# R302L.net
KiCad netlist of a schematic drawn in EAGLE
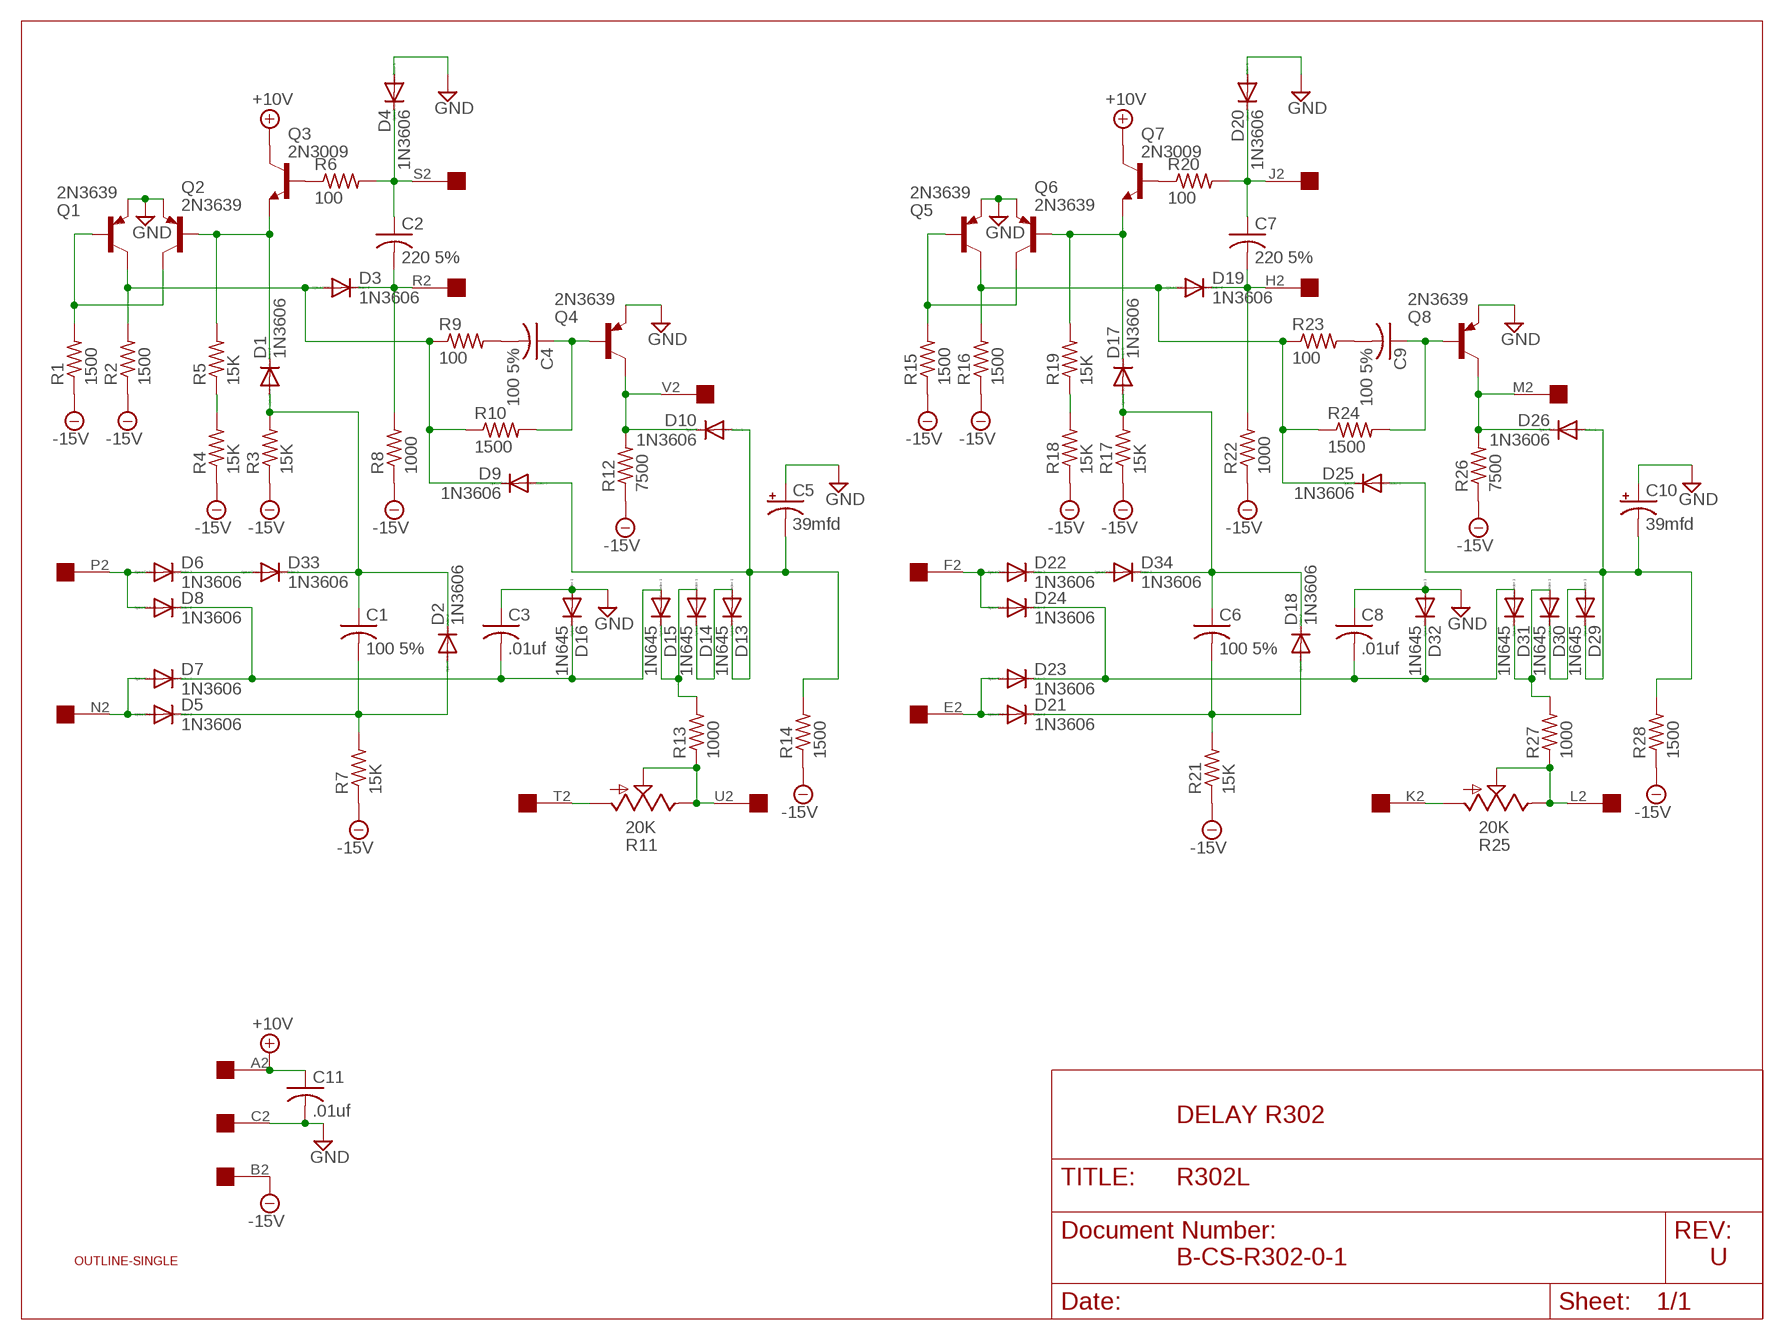
[diagram p0: schematic, sheet 1]

(export (version "E")
  (design (tool "Eeschema 10.0.6"))
  (components
    (comp (ref "C1")
      (value "100 5%")
      (footprint "eagle-import:C050-025X075")
      (libsource (lib "eagle-import") (part "C-US050-025X075"))
    )
    (comp (ref "C2")
      (value "220 5%")
      (footprint "eagle-import:C050-025X075")
      (libsource (lib "eagle-import") (part "C-US050-025X075"))
    )
    (comp (ref "C3")
      (value ".01uf")
      (footprint "eagle-import:C050-025X075")
      (libsource (lib "eagle-import") (part "C-US050-025X075"))
    )
    (comp (ref "C4")
      (value "100 5%")
      (footprint "eagle-import:C050-025X075")
      (libsource (lib "eagle-import") (part "C-US050-025X075"))
    )
    (comp (ref "C5")
      (value "39mfd")
      (footprint "eagle-import:E15-5")
      (libsource (lib "eagle-import") (part "CPOL-USE15-5AXIAL"))
    )
    (comp (ref "C6")
      (value "100 5%")
      (footprint "eagle-import:C050-025X075")
      (libsource (lib "eagle-import") (part "C-US050-025X075"))
    )
    (comp (ref "C7")
      (value "220 5%")
      (footprint "eagle-import:C050-025X075")
      (libsource (lib "eagle-import") (part "C-US050-025X075"))
    )
    (comp (ref "C8")
      (value ".01uf")
      (footprint "eagle-import:C050-025X075")
      (libsource (lib "eagle-import") (part "C-US050-025X075"))
    )
    (comp (ref "C9")
      (value "100 5%")
      (footprint "eagle-import:C050-025X075")
      (libsource (lib "eagle-import") (part "C-US050-025X075"))
    )
    (comp (ref "C10")
      (value "39mfd")
      (footprint "eagle-import:E15-5")
      (libsource (lib "eagle-import") (part "CPOL-USE15-5AXIAL"))
    )
    (comp (ref "C11")
      (value ".01uf")
      (footprint "eagle-import:C050-025X075")
      (libsource (lib "eagle-import") (part "C-US050-025X075"))
    )
    (comp (ref "D1")
      (value "1N3606")
      (footprint "eagle-import:DO35-10")
      (libsource (lib "eagle-import") (part "1N4148DO35-10"))
    )
    (comp (ref "D2")
      (value "1N3606")
      (footprint "eagle-import:DO35-10")
      (libsource (lib "eagle-import") (part "1N4148DO35-10"))
    )
    (comp (ref "D3")
      (value "1N3606")
      (footprint "eagle-import:DO35-10")
      (libsource (lib "eagle-import") (part "1N4148DO35-10"))
    )
    (comp (ref "D4")
      (value "1N3606")
      (footprint "eagle-import:DO35-10")
      (libsource (lib "eagle-import") (part "1N4148DO35-10"))
    )
    (comp (ref "D5")
      (value "1N3606")
      (footprint "eagle-import:DO35-10")
      (libsource (lib "eagle-import") (part "1N4148DO35-10"))
    )
    (comp (ref "D6")
      (value "1N3606")
      (footprint "eagle-import:DO35-10")
      (libsource (lib "eagle-import") (part "1N4148DO35-10"))
    )
    (comp (ref "D7")
      (value "1N3606")
      (footprint "eagle-import:DO35-10")
      (libsource (lib "eagle-import") (part "1N4148DO35-10"))
    )
    (comp (ref "D8")
      (value "1N3606")
      (footprint "eagle-import:DO35-10")
      (libsource (lib "eagle-import") (part "1N4148DO35-10"))
    )
    (comp (ref "D9")
      (value "1N3606")
      (footprint "eagle-import:DO35-10")
      (libsource (lib "eagle-import") (part "1N4148DO35-10"))
    )
    (comp (ref "D10")
      (value "1N3606")
      (footprint "eagle-import:DO35-10")
      (libsource (lib "eagle-import") (part "1N4148DO35-10"))
    )
    (comp (ref "D13")
      (value "1N645")
      (footprint "eagle-import:DO35-10")
      (libsource (lib "eagle-import") (part "1N4148DO35-10"))
    )
    (comp (ref "D14")
      (value "1N645")
      (footprint "eagle-import:DO35-10")
      (libsource (lib "eagle-import") (part "1N4148DO35-10"))
    )
    (comp (ref "D15")
      (value "1N645")
      (footprint "eagle-import:DO35-10")
      (libsource (lib "eagle-import") (part "1N4148DO35-10"))
    )
    (comp (ref "D16")
      (value "1N645")
      (footprint "eagle-import:DO35-10")
      (libsource (lib "eagle-import") (part "1N4148DO35-10"))
    )
    (comp (ref "D17")
      (value "1N3606")
      (footprint "eagle-import:DO35-10")
      (libsource (lib "eagle-import") (part "1N4148DO35-10"))
    )
    (comp (ref "D18")
      (value "1N3606")
      (footprint "eagle-import:DO35-10")
      (libsource (lib "eagle-import") (part "1N4148DO35-10"))
    )
    (comp (ref "D19")
      (value "1N3606")
      (footprint "eagle-import:DO35-10")
      (libsource (lib "eagle-import") (part "1N4148DO35-10"))
    )
    (comp (ref "D20")
      (value "1N3606")
      (footprint "eagle-import:DO35-10")
      (libsource (lib "eagle-import") (part "1N4148DO35-10"))
    )
    (comp (ref "D21")
      (value "1N3606")
      (footprint "eagle-import:DO35-10")
      (libsource (lib "eagle-import") (part "1N4148DO35-10"))
    )
    (comp (ref "D22")
      (value "1N3606")
      (footprint "eagle-import:DO35-10")
      (libsource (lib "eagle-import") (part "1N4148DO35-10"))
    )
    (comp (ref "D23")
      (value "1N3606")
      (footprint "eagle-import:DO35-10")
      (libsource (lib "eagle-import") (part "1N4148DO35-10"))
    )
    (comp (ref "D24")
      (value "1N3606")
      (footprint "eagle-import:DO35-10")
      (libsource (lib "eagle-import") (part "1N4148DO35-10"))
    )
    (comp (ref "D25")
      (value "1N3606")
      (footprint "eagle-import:DO35-10")
      (libsource (lib "eagle-import") (part "1N4148DO35-10"))
    )
    (comp (ref "D26")
      (value "1N3606")
      (footprint "eagle-import:DO35-10")
      (libsource (lib "eagle-import") (part "1N4148DO35-10"))
    )
    (comp (ref "D29")
      (value "1N645")
      (footprint "eagle-import:DO35-10")
      (libsource (lib "eagle-import") (part "1N4148DO35-10"))
    )
    (comp (ref "D30")
      (value "1N645")
      (footprint "eagle-import:DO35-10")
      (libsource (lib "eagle-import") (part "1N4148DO35-10"))
    )
    (comp (ref "D31")
      (value "1N645")
      (footprint "eagle-import:DO35-10")
      (libsource (lib "eagle-import") (part "1N4148DO35-10"))
    )
    (comp (ref "D32")
      (value "1N645")
      (footprint "eagle-import:DO35-10")
      (libsource (lib "eagle-import") (part "1N4148DO35-10"))
    )
    (comp (ref "D33")
      (value "1N3606")
      (footprint "eagle-import:DO35-10")
      (libsource (lib "eagle-import") (part "1N4148DO35-10"))
    )
    (comp (ref "D34")
      (value "1N3606")
      (footprint "eagle-import:DO35-10")
      (libsource (lib "eagle-import") (part "1N4148DO35-10"))
    )
    (comp (ref "Q1")
      (value "2N3639")
      (footprint "eagle-import:TO39")
      (libsource (lib "eagle-import") (part "2N3637"))
    )
    (comp (ref "Q2")
      (value "2N3639")
      (footprint "eagle-import:TO39")
      (libsource (lib "eagle-import") (part "2N3637"))
    )
    (comp (ref "Q3")
      (value "2N3009")
      (footprint "eagle-import:TO39")
      (libsource (lib "eagle-import") (part "-NPN-TO39-EBC2N3019"))
    )
    (comp (ref "Q4")
      (value "2N3639")
      (footprint "eagle-import:TO39")
      (libsource (lib "eagle-import") (part "2N3637"))
    )
    (comp (ref "Q5")
      (value "2N3639")
      (footprint "eagle-import:TO39")
      (libsource (lib "eagle-import") (part "2N3637"))
    )
    (comp (ref "Q6")
      (value "2N3639")
      (footprint "eagle-import:TO39")
      (libsource (lib "eagle-import") (part "2N3637"))
    )
    (comp (ref "Q7")
      (value "2N3009")
      (footprint "eagle-import:TO39")
      (libsource (lib "eagle-import") (part "-NPN-TO39-EBC2N3019"))
    )
    (comp (ref "Q8")
      (value "2N3639")
      (footprint "eagle-import:TO39")
      (libsource (lib "eagle-import") (part "2N3637"))
    )
    (comp (ref "R1")
      (value "1500")
      (footprint "eagle-import:0207_10")
      (libsource (lib "eagle-import") (part "R-US_0207/10"))
    )
    (comp (ref "R2")
      (value "1500")
      (footprint "eagle-import:0207_10")
      (libsource (lib "eagle-import") (part "R-US_0207/10"))
    )
    (comp (ref "R3")
      (value "15K")
      (footprint "eagle-import:0207_10")
      (libsource (lib "eagle-import") (part "R-US_0207/10"))
    )
    (comp (ref "R4")
      (value "15K")
      (footprint "eagle-import:0207_10")
      (libsource (lib "eagle-import") (part "R-US_0207/10"))
    )
    (comp (ref "R5")
      (value "15K")
      (footprint "eagle-import:0207_10")
      (libsource (lib "eagle-import") (part "R-US_0207/10"))
    )
    (comp (ref "R6")
      (value "100")
      (footprint "eagle-import:0207_10")
      (libsource (lib "eagle-import") (part "R-US_0207/10"))
    )
    (comp (ref "R7")
      (value "15K")
      (footprint "eagle-import:0207_10")
      (libsource (lib "eagle-import") (part "R-US_0207/10"))
    )
    (comp (ref "R8")
      (value "1000")
      (footprint "eagle-import:0207_10")
      (libsource (lib "eagle-import") (part "R-US_0207/10"))
    )
    (comp (ref "R9")
      (value "100")
      (footprint "eagle-import:0207_10")
      (libsource (lib "eagle-import") (part "R-US_0207/10"))
    )
    (comp (ref "R10")
      (value "1500")
      (footprint "eagle-import:0207_10")
      (libsource (lib "eagle-import") (part "R-US_0207/10"))
    )
    (comp (ref "R11")
      (value "20K")
      (footprint "eagle-import:SP19L")
      (libsource (lib "eagle-import") (part "TRIM_US-S43P"))
    )
    (comp (ref "R12")
      (value "7500")
      (footprint "eagle-import:0207_10")
      (libsource (lib "eagle-import") (part "R-US_0207/10"))
    )
    (comp (ref "R13")
      (value "1000")
      (footprint "eagle-import:0207_10")
      (libsource (lib "eagle-import") (part "R-US_0207/10"))
    )
    (comp (ref "R14")
      (value "1500")
      (footprint "eagle-import:0207_10")
      (libsource (lib "eagle-import") (part "R-US_0207/10"))
    )
    (comp (ref "R15")
      (value "1500")
      (footprint "eagle-import:0207_10")
      (libsource (lib "eagle-import") (part "R-US_0207/10"))
    )
    (comp (ref "R16")
      (value "1500")
      (footprint "eagle-import:0207_10")
      (libsource (lib "eagle-import") (part "R-US_0207/10"))
    )
    (comp (ref "R17")
      (value "15K")
      (footprint "eagle-import:0207_10")
      (libsource (lib "eagle-import") (part "R-US_0207/10"))
    )
    (comp (ref "R18")
      (value "15K")
      (footprint "eagle-import:0207_10")
      (libsource (lib "eagle-import") (part "R-US_0207/10"))
    )
    (comp (ref "R19")
      (value "15K")
      (footprint "eagle-import:0207_10")
      (libsource (lib "eagle-import") (part "R-US_0207/10"))
    )
    (comp (ref "R20")
      (value "100")
      (footprint "eagle-import:0207_10")
      (libsource (lib "eagle-import") (part "R-US_0207/10"))
    )
    (comp (ref "R21")
      (value "15K")
      (footprint "eagle-import:0207_10")
      (libsource (lib "eagle-import") (part "R-US_0207/10"))
    )
    (comp (ref "R22")
      (value "1000")
      (footprint "eagle-import:0207_10")
      (libsource (lib "eagle-import") (part "R-US_0207/10"))
    )
    (comp (ref "R23")
      (value "100")
      (footprint "eagle-import:0207_10")
      (libsource (lib "eagle-import") (part "R-US_0207/10"))
    )
    (comp (ref "R24")
      (value "1500")
      (footprint "eagle-import:0207_10")
      (libsource (lib "eagle-import") (part "R-US_0207/10"))
    )
    (comp (ref "R25")
      (value "20K")
      (footprint "eagle-import:SP19L")
      (libsource (lib "eagle-import") (part "TRIM_US-S43P"))
    )
    (comp (ref "R26")
      (value "7500")
      (footprint "eagle-import:0207_10")
      (libsource (lib "eagle-import") (part "R-US_0207/10"))
    )
    (comp (ref "R27")
      (value "1000")
      (footprint "eagle-import:0207_10")
      (libsource (lib "eagle-import") (part "R-US_0207/10"))
    )
    (comp (ref "R28")
      (value "1500")
      (footprint "eagle-import:0207_10")
      (libsource (lib "eagle-import") (part "R-US_0207/10"))
    )
    (comp (ref "U$1")
      (value "OUTLINE-SINGLE")
      (footprint "eagle-import:SINGLE")
      (libsource (lib "eagle-import") (part "OUTLINE-SINGLE"))
    )
    (comp (ref "U$2")
      (value "EDGE-1")
      (footprint "eagle-import:EDGE-CON1")
      (libsource (lib "eagle-import") (part "EDGE-1"))
    )
  )
  (nets
    (net (code "1") (name "+10V") (class "Default")
      (node (ref "C11") (pin "1") (pinfunction "1_1") (pintype "passive"))
      (node (ref "Q3") (pin "3") (pinfunction "C_3") (pintype "passive"))
      (node (ref "Q7") (pin "3") (pinfunction "C_3") (pintype "passive"))
      (node (ref "U$2") (pin "A2") (pinfunction "1_A2") (pintype "bidirectional"))
    )
    (net (code "2") (name "-15V") (class "Default")
      (node (ref "R1") (pin "1") (pinfunction "1_1") (pintype "passive"))
      (node (ref "R12") (pin "1") (pinfunction "1_1") (pintype "passive"))
      (node (ref "R14") (pin "1") (pinfunction "1_1") (pintype "passive"))
      (node (ref "R15") (pin "1") (pinfunction "1_1") (pintype "passive"))
      (node (ref "R16") (pin "1") (pinfunction "1_1") (pintype "passive"))
      (node (ref "R17") (pin "1") (pinfunction "1_1") (pintype "passive"))
      (node (ref "R18") (pin "1") (pinfunction "1_1") (pintype "passive"))
      (node (ref "R2") (pin "1") (pinfunction "1_1") (pintype "passive"))
      (node (ref "R21") (pin "1") (pinfunction "1_1") (pintype "passive"))
      (node (ref "R22") (pin "1") (pinfunction "1_1") (pintype "passive"))
      (node (ref "R26") (pin "1") (pinfunction "1_1") (pintype "passive"))
      (node (ref "R28") (pin "1") (pinfunction "1_1") (pintype "passive"))
      (node (ref "R3") (pin "1") (pinfunction "1_1") (pintype "passive"))
      (node (ref "R4") (pin "1") (pinfunction "1_1") (pintype "passive"))
      (node (ref "R7") (pin "1") (pinfunction "1_1") (pintype "passive"))
      (node (ref "R8") (pin "1") (pinfunction "1_1") (pintype "passive"))
      (node (ref "U$2") (pin "B2") (pinfunction "1_B2") (pintype "bidirectional"))
    )
    (net (code "3") (name "GND") (class "Default")
      (node (ref "C10") (pin "+") (pinfunction "+_+") (pintype "passive"))
      (node (ref "C11") (pin "2") (pinfunction "2_2") (pintype "passive"))
      (node (ref "C3") (pin "1") (pinfunction "1_1") (pintype "passive"))
      (node (ref "C5") (pin "+") (pinfunction "+_+") (pintype "passive"))
      (node (ref "C8") (pin "1") (pinfunction "1_1") (pintype "passive"))
      (node (ref "D16") (pin "A") (pinfunction "A_A") (pintype "passive"))
      (node (ref "D20") (pin "A") (pinfunction "A_A") (pintype "passive"))
      (node (ref "D32") (pin "A") (pinfunction "A_A") (pintype "passive"))
      (node (ref "D4") (pin "A") (pinfunction "A_A") (pintype "passive"))
      (node (ref "Q1") (pin "1") (pinfunction "E_1") (pintype "passive"))
      (node (ref "Q2") (pin "1") (pinfunction "E_1") (pintype "passive"))
      (node (ref "Q4") (pin "1") (pinfunction "E_1") (pintype "passive"))
      (node (ref "Q5") (pin "1") (pinfunction "E_1") (pintype "passive"))
      (node (ref "Q6") (pin "1") (pinfunction "E_1") (pintype "passive"))
      (node (ref "Q8") (pin "1") (pinfunction "E_1") (pintype "passive"))
      (node (ref "U$2") (pin "C2") (pinfunction "1_C2") (pintype "bidirectional"))
    )
    (net (code "4") (name "Net-(C1-Pad1)") (class "Default")
      (node (ref "C1") (pin "1") (pinfunction "1_1") (pintype "passive"))
      (node (ref "D1") (pin "A") (pinfunction "A_A") (pintype "passive"))
      (node (ref "D2") (pin "C") (pinfunction "C_C") (pintype "passive"))
      (node (ref "D33") (pin "C") (pinfunction "C_C") (pintype "passive"))
      (node (ref "R3") (pin "2") (pinfunction "2_2") (pintype "passive"))
    )
    (net (code "5") (name "Net-(C1-Pad2)") (class "Default")
      (node (ref "C1") (pin "2") (pinfunction "2_2") (pintype "passive"))
      (node (ref "D2") (pin "A") (pinfunction "A_A") (pintype "passive"))
      (node (ref "D5") (pin "C") (pinfunction "C_C") (pintype "passive"))
      (node (ref "R7") (pin "2") (pinfunction "2_2") (pintype "passive"))
    )
    (net (code "6") (name "Net-(C3-Pad2)") (class "Default")
      (node (ref "C3") (pin "2") (pinfunction "2_2") (pintype "passive"))
      (node (ref "D15") (pin "A") (pinfunction "A_A") (pintype "passive"))
      (node (ref "D16") (pin "C") (pinfunction "C_C") (pintype "passive"))
      (node (ref "D7") (pin "C") (pinfunction "C_C") (pintype "passive"))
      (node (ref "D8") (pin "C") (pinfunction "C_C") (pintype "passive"))
    )
    (net (code "7") (name "Net-(C4-Pad2)") (class "Default")
      (node (ref "C4") (pin "2") (pinfunction "2_2") (pintype "passive"))
      (node (ref "R9") (pin "2") (pinfunction "2_2") (pintype "passive"))
    )
    (net (code "8") (name "Net-(C5-Pad-)") (class "Default")
      (node (ref "C5") (pin "-") (pinfunction "-_-") (pintype "passive"))
      (node (ref "D10") (pin "A") (pinfunction "A_A") (pintype "passive"))
      (node (ref "D13") (pin "C") (pinfunction "C_C") (pintype "passive"))
      (node (ref "D9") (pin "A") (pinfunction "A_A") (pintype "passive"))
      (node (ref "R14") (pin "2") (pinfunction "2_2") (pintype "passive"))
    )
    (net (code "9") (name "Net-(C6-Pad1)") (class "Default")
      (node (ref "C6") (pin "1") (pinfunction "1_1") (pintype "passive"))
      (node (ref "D17") (pin "A") (pinfunction "A_A") (pintype "passive"))
      (node (ref "D18") (pin "C") (pinfunction "C_C") (pintype "passive"))
      (node (ref "D34") (pin "C") (pinfunction "C_C") (pintype "passive"))
      (node (ref "R17") (pin "2") (pinfunction "2_2") (pintype "passive"))
    )
    (net (code "10") (name "Net-(C6-Pad2)") (class "Default")
      (node (ref "C6") (pin "2") (pinfunction "2_2") (pintype "passive"))
      (node (ref "D18") (pin "A") (pinfunction "A_A") (pintype "passive"))
      (node (ref "D21") (pin "C") (pinfunction "C_C") (pintype "passive"))
      (node (ref "R21") (pin "2") (pinfunction "2_2") (pintype "passive"))
    )
    (net (code "11") (name "Net-(C8-Pad2)") (class "Default")
      (node (ref "C8") (pin "2") (pinfunction "2_2") (pintype "passive"))
      (node (ref "D23") (pin "C") (pinfunction "C_C") (pintype "passive"))
      (node (ref "D24") (pin "C") (pinfunction "C_C") (pintype "passive"))
      (node (ref "D31") (pin "A") (pinfunction "A_A") (pintype "passive"))
      (node (ref "D32") (pin "C") (pinfunction "C_C") (pintype "passive"))
    )
    (net (code "12") (name "Net-(C9-Pad2)") (class "Default")
      (node (ref "C9") (pin "2") (pinfunction "2_2") (pintype "passive"))
      (node (ref "R23") (pin "2") (pinfunction "2_2") (pintype "passive"))
    )
    (net (code "13") (name "Net-(C10-Pad-)") (class "Default")
      (node (ref "C10") (pin "-") (pinfunction "-_-") (pintype "passive"))
      (node (ref "D25") (pin "A") (pinfunction "A_A") (pintype "passive"))
      (node (ref "D26") (pin "A") (pinfunction "A_A") (pintype "passive"))
      (node (ref "D29") (pin "C") (pinfunction "C_C") (pintype "passive"))
      (node (ref "R28") (pin "2") (pinfunction "2_2") (pintype "passive"))
    )
    (net (code "14") (name "Net-(D13-PadA)") (class "Default")
      (node (ref "D13") (pin "A") (pinfunction "A_A") (pintype "passive"))
      (node (ref "D14") (pin "C") (pinfunction "C_C") (pintype "passive"))
    )
    (net (code "15") (name "Net-(D14-PadA)") (class "Default")
      (node (ref "D14") (pin "A") (pinfunction "A_A") (pintype "passive"))
      (node (ref "D15") (pin "C") (pinfunction "C_C") (pintype "passive"))
      (node (ref "R13") (pin "2") (pinfunction "2_2") (pintype "passive"))
    )
    (net (code "16") (name "Net-(D22-PadC)") (class "Default")
      (node (ref "D22") (pin "C") (pinfunction "C_C") (pintype "passive"))
      (node (ref "D34") (pin "A") (pinfunction "A_A") (pintype "passive"))
    )
    (net (code "17") (name "Net-(D29-PadA)") (class "Default")
      (node (ref "D29") (pin "A") (pinfunction "A_A") (pintype "passive"))
      (node (ref "D30") (pin "C") (pinfunction "C_C") (pintype "passive"))
    )
    (net (code "18") (name "Net-(D30-PadA)") (class "Default")
      (node (ref "D30") (pin "A") (pinfunction "A_A") (pintype "passive"))
      (node (ref "D31") (pin "C") (pinfunction "C_C") (pintype "passive"))
      (node (ref "R27") (pin "2") (pinfunction "2_2") (pintype "passive"))
    )
    (net (code "19") (name "Net-(D33-PadA)") (class "Default")
      (node (ref "D33") (pin "A") (pinfunction "A_A") (pintype "passive"))
      (node (ref "D6") (pin "C") (pinfunction "C_C") (pintype "passive"))
    )
    (net (code "20") (name "Net-(Q1-B)") (class "Default")
      (node (ref "Q1") (pin "2") (pinfunction "B_2") (pintype "passive"))
      (node (ref "Q2") (pin "3") (pinfunction "C_3") (pintype "passive"))
      (node (ref "R1") (pin "2") (pinfunction "2_2") (pintype "passive"))
    )
    (net (code "21") (name "Net-(Q1-C)") (class "Default")
      (node (ref "D3") (pin "A") (pinfunction "A_A") (pintype "passive"))
      (node (ref "D9") (pin "C") (pinfunction "C_C") (pintype "passive"))
      (node (ref "Q1") (pin "3") (pinfunction "C_3") (pintype "passive"))
      (node (ref "R10") (pin "1") (pinfunction "1_1") (pintype "passive"))
      (node (ref "R2") (pin "2") (pinfunction "2_2") (pintype "passive"))
      (node (ref "R9") (pin "1") (pinfunction "1_1") (pintype "passive"))
    )
    (net (code "22") (name "Net-(Q2-B)") (class "Default")
      (node (ref "D1") (pin "C") (pinfunction "C_C") (pintype "passive"))
      (node (ref "Q2") (pin "2") (pinfunction "B_2") (pintype "passive"))
      (node (ref "Q3") (pin "1") (pinfunction "E_1") (pintype "passive"))
      (node (ref "R5") (pin "2") (pinfunction "2_2") (pintype "passive"))
    )
    (net (code "23") (name "Net-(Q3-B)") (class "Default")
      (node (ref "Q3") (pin "2") (pinfunction "B_2") (pintype "passive"))
      (node (ref "R6") (pin "1") (pinfunction "1_1") (pintype "passive"))
    )
    (net (code "24") (name "Net-(Q4-B)") (class "Default")
      (node (ref "C4") (pin "1") (pinfunction "1_1") (pintype "passive"))
      (node (ref "Q4") (pin "2") (pinfunction "B_2") (pintype "passive"))
      (node (ref "R10") (pin "2") (pinfunction "2_2") (pintype "passive"))
    )
    (net (code "25") (name "Net-(Q4-C)") (class "Default")
      (node (ref "D10") (pin "C") (pinfunction "C_C") (pintype "passive"))
      (node (ref "Q4") (pin "3") (pinfunction "C_3") (pintype "passive"))
      (node (ref "R12") (pin "2") (pinfunction "2_2") (pintype "passive"))
      (node (ref "U$2") (pin "V2") (pinfunction "1_V2") (pintype "bidirectional"))
    )
    (net (code "26") (name "Net-(Q5-B)") (class "Default")
      (node (ref "Q5") (pin "2") (pinfunction "B_2") (pintype "passive"))
      (node (ref "Q6") (pin "3") (pinfunction "C_3") (pintype "passive"))
      (node (ref "R15") (pin "2") (pinfunction "2_2") (pintype "passive"))
    )
    (net (code "27") (name "Net-(Q5-C)") (class "Default")
      (node (ref "D19") (pin "A") (pinfunction "A_A") (pintype "passive"))
      (node (ref "D25") (pin "C") (pinfunction "C_C") (pintype "passive"))
      (node (ref "Q5") (pin "3") (pinfunction "C_3") (pintype "passive"))
      (node (ref "R16") (pin "2") (pinfunction "2_2") (pintype "passive"))
      (node (ref "R23") (pin "1") (pinfunction "1_1") (pintype "passive"))
      (node (ref "R24") (pin "1") (pinfunction "1_1") (pintype "passive"))
    )
    (net (code "28") (name "Net-(Q6-B)") (class "Default")
      (node (ref "D17") (pin "C") (pinfunction "C_C") (pintype "passive"))
      (node (ref "Q6") (pin "2") (pinfunction "B_2") (pintype "passive"))
      (node (ref "Q7") (pin "1") (pinfunction "E_1") (pintype "passive"))
      (node (ref "R19") (pin "2") (pinfunction "2_2") (pintype "passive"))
    )
    (net (code "29") (name "Net-(Q7-B)") (class "Default")
      (node (ref "Q7") (pin "2") (pinfunction "B_2") (pintype "passive"))
      (node (ref "R20") (pin "1") (pinfunction "1_1") (pintype "passive"))
    )
    (net (code "30") (name "Net-(Q8-B)") (class "Default")
      (node (ref "C9") (pin "1") (pinfunction "1_1") (pintype "passive"))
      (node (ref "Q8") (pin "2") (pinfunction "B_2") (pintype "passive"))
      (node (ref "R24") (pin "2") (pinfunction "2_2") (pintype "passive"))
    )
    (net (code "31") (name "Net-(Q8-C)") (class "Default")
      (node (ref "D26") (pin "C") (pinfunction "C_C") (pintype "passive"))
      (node (ref "Q8") (pin "3") (pinfunction "C_3") (pintype "passive"))
      (node (ref "R26") (pin "2") (pinfunction "2_2") (pintype "passive"))
      (node (ref "U$2") (pin "M2") (pinfunction "1_M2") (pintype "bidirectional"))
    )
    (net (code "32") (name "Net-(R4-Pad2)") (class "Default")
      (node (ref "R4") (pin "2") (pinfunction "2_2") (pintype "passive"))
      (node (ref "R5") (pin "1") (pinfunction "1_1") (pintype "passive"))
    )
    (net (code "33") (name "Net-(R18-Pad2)") (class "Default")
      (node (ref "R18") (pin "2") (pinfunction "2_2") (pintype "passive"))
      (node (ref "R19") (pin "1") (pinfunction "1_1") (pintype "passive"))
    )
    (net (code "34") (name "Net-(U$2E-1)") (class "Default")
      (node (ref "D21") (pin "A") (pinfunction "A_A") (pintype "passive"))
      (node (ref "D23") (pin "A") (pinfunction "A_A") (pintype "passive"))
      (node (ref "U$2") (pin "E2") (pinfunction "1_E2") (pintype "bidirectional"))
    )
    (net (code "35") (name "Net-(U$2F-1)") (class "Default")
      (node (ref "D22") (pin "A") (pinfunction "A_A") (pintype "passive"))
      (node (ref "D24") (pin "A") (pinfunction "A_A") (pintype "passive"))
      (node (ref "U$2") (pin "F2") (pinfunction "1_F2") (pintype "bidirectional"))
    )
    (net (code "36") (name "Net-(U$2G-1)") (class "Default")
      (node (ref "C7") (pin "2") (pinfunction "2_2") (pintype "passive"))
      (node (ref "D19") (pin "C") (pinfunction "C_C") (pintype "passive"))
      (node (ref "R22") (pin "2") (pinfunction "2_2") (pintype "passive"))
      (node (ref "U$2") (pin "H2") (pinfunction "1_H2") (pintype "bidirectional"))
    )
    (net (code "37") (name "Net-(U$2H-1)") (class "Default")
      (node (ref "C7") (pin "1") (pinfunction "1_1") (pintype "passive"))
      (node (ref "D20") (pin "C") (pinfunction "C_C") (pintype "passive"))
      (node (ref "R20") (pin "2") (pinfunction "2_2") (pintype "passive"))
      (node (ref "U$2") (pin "J2") (pinfunction "1_J2") (pintype "bidirectional"))
    )
    (net (code "38") (name "Net-(U$2I-1)") (class "Default")
      (node (ref "R25") (pin "A") (pinfunction "A_A") (pintype "passive"))
      (node (ref "U$2") (pin "K2") (pinfunction "1_K2") (pintype "bidirectional"))
    )
    (net (code "39") (name "Net-(U$2J-1)") (class "Default")
      (node (ref "R25") (pin "E") (pinfunction "E_E") (pintype "passive"))
      (node (ref "R25") (pin "S") (pinfunction "S_S") (pintype "passive"))
      (node (ref "R27") (pin "1") (pinfunction "1_1") (pintype "passive"))
      (node (ref "U$2") (pin "L2") (pinfunction "1_L2") (pintype "bidirectional"))
    )
    (net (code "40") (name "Net-(U$2L-1)") (class "Default")
      (node (ref "D5") (pin "A") (pinfunction "A_A") (pintype "passive"))
      (node (ref "D7") (pin "A") (pinfunction "A_A") (pintype "passive"))
      (node (ref "U$2") (pin "N2") (pinfunction "1_N2") (pintype "bidirectional"))
    )
    (net (code "41") (name "Net-(U$2M-1)") (class "Default")
      (node (ref "D6") (pin "A") (pinfunction "A_A") (pintype "passive"))
      (node (ref "D8") (pin "A") (pinfunction "A_A") (pintype "passive"))
      (node (ref "U$2") (pin "P2") (pinfunction "1_P2") (pintype "bidirectional"))
    )
    (net (code "42") (name "Net-(U$2N-1)") (class "Default")
      (node (ref "C2") (pin "2") (pinfunction "2_2") (pintype "passive"))
      (node (ref "D3") (pin "C") (pinfunction "C_C") (pintype "passive"))
      (node (ref "R8") (pin "2") (pinfunction "2_2") (pintype "passive"))
      (node (ref "U$2") (pin "R2") (pinfunction "1_R2") (pintype "bidirectional"))
    )
    (net (code "43") (name "Net-(U$2O-1)") (class "Default")
      (node (ref "C2") (pin "1") (pinfunction "1_1") (pintype "passive"))
      (node (ref "D4") (pin "C") (pinfunction "C_C") (pintype "passive"))
      (node (ref "R6") (pin "2") (pinfunction "2_2") (pintype "passive"))
      (node (ref "U$2") (pin "S2") (pinfunction "1_S2") (pintype "bidirectional"))
    )
    (net (code "44") (name "Net-(U$2P-1)") (class "Default")
      (node (ref "R11") (pin "A") (pinfunction "A_A") (pintype "passive"))
      (node (ref "U$2") (pin "T2") (pinfunction "1_T2") (pintype "bidirectional"))
    )
    (net (code "45") (name "Net-(U$2Q-1)") (class "Default")
      (node (ref "R11") (pin "E") (pinfunction "E_E") (pintype "passive"))
      (node (ref "R11") (pin "S") (pinfunction "S_S") (pintype "passive"))
      (node (ref "R13") (pin "1") (pinfunction "1_1") (pintype "passive"))
      (node (ref "U$2") (pin "U2") (pinfunction "1_U2") (pintype "bidirectional"))
    )
  )
)
